# MDL_FUENTE_5V.net
KiCad netlist of a schematic drawn in Altium Designer
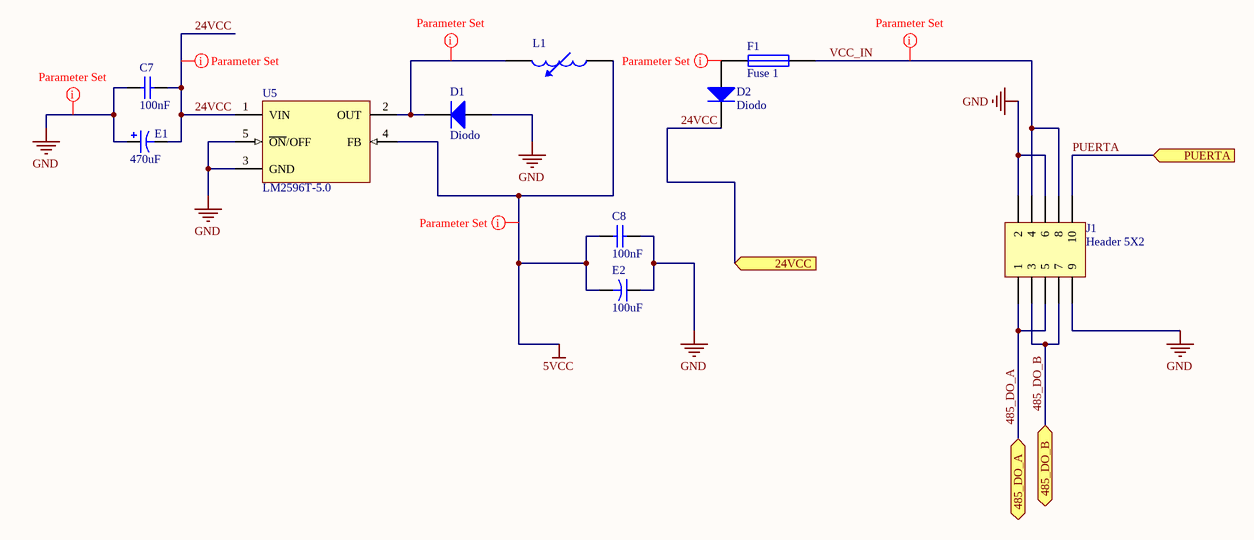
[diagram p0: MDL_FUENTE_5V.SchDoc]

(export (version "E")
  (design (tool "Eeschema 10.0.6"))
  (components
    (comp (ref "C7")
      (value "100nF")
      (footprint "VP44-2.5")
      (description "Dipped Radial Multilayer Ceramic Capacitor X7R: 220nF, 100V")
      (fields (field (name "Comment") "VP44BY224JB") (field (name "PUBLISHER") "Altium Limited"))
      (libsource (lib "Vishay Vitramon Ceramic Dipped Capacitor") (part "VP44BY224JB"))
    )
    (comp (ref "C8")
      (value "100nF")
      (footprint "VP44-2.5")
      (description "Dipped Radial Multilayer Ceramic Capacitor X7R: 220nF, 100V")
      (fields (field (name "Comment") "VP44BY224JB") (field (name "PUBLISHER") "Altium Limited"))
      (libsource (lib "Vishay Vitramon Ceramic Dipped Capacitor") (part "VP44BY224JB"))
    )
    (comp (ref "D1")
      (value "Diodo")
      (footprint "1N4000")
      (description "Diodo rectificador")
      (libsource (lib "Diodos") (part "Diodo"))
    )
    (comp (ref "D2")
      (value "Diodo")
      (footprint "1N4000")
      (description "Diodo rectificador")
      (libsource (lib "Diodos") (part "Diodo"))
    )
    (comp (ref "E1")
      (value "470uF")
      (footprint "C1000UF")
      (description "Polarized Capacitor (Radial)")
      (fields (field (name "Comment") "Cap Pol1") (field (name "PUBLISHER") "Altium Limited"))
      (libsource (lib "Miscellaneous Devices") (part "Cap Pol1"))
    )
    (comp (ref "E2")
      (value "100uF")
      (footprint "C1UF")
      (description "Capacitor")
      (fields (field (name "Comment") "Cap2") (field (name "PUBLISHER") "Altium Limited"))
      (libsource (lib "Miscellaneous Devices") (part "Cap2"))
    )
    (comp (ref "F1")
      (value "Fuse 1")
      (footprint "FUSIBLE_BUSMATIC")
      (description "Fuse")
      (fields (field (name "PUBLISHER") "Altium Limited"))
      (libsource (lib "Miscellaneous Devices") (part "Fuse 1"))
    )
    (comp (ref "J1")
      (value "Header 5X2")
      (footprint "FP_CON10")
      (description "Header, 5-Pin, Dual row")
      (fields (field (name "PUBLISHER") "Altium Limited"))
      (libsource (lib "Miscellaneous Connectors") (part "Header 5X2"))
    )
    (comp (ref "L1")
      (value "Inductor Adj")
      (footprint "Inductor_redondo")
      (description "Adjustable Inductor")
      (fields (field (name "PUBLISHER") "Altium Limited"))
      (libsource (lib "Miscellaneous Devices") (part "Inductor Adj"))
    )
    (comp (ref "U5")
      (value "LM2596T-5.0")
      (footprint "FP_LM2596_D_PCB")
      (description "SIMPLE SWITCHER Power Converter 150 KHz 3A Step-Down Voltage Regulator")
      (fields
        (field (name "MANUFACTURER") "National Semiconductor")
        (field (name "DIGIKEYPARTNUMBER") "LM2596T-5.0-ND")
        (field (name "PUBLISHER") "Altium Limited")
      )
      (libsource (lib "NSC Switcher") (part "LM2596T-5.0"))
    )
  )
  (nets
    (net (code "1") (name "/24VCC") (class "Default")
      (node (ref "C7") (pin "1") (pinfunction "1_1") (pintype "passive"))
      (node (ref "D2") (pin "2") (pinfunction "K_2") (pintype "passive"))
      (node (ref "E1") (pin "2") (pinfunction "2_2") (pintype "passive"))
      (node (ref "U5") (pin "1") (pinfunction "VIN_1") (pintype "power_in"))
    )
    (net (code "2") (name "/485_DO_A") (class "Default")
      (node (ref "J1") (pin "1") (pinfunction "1_1") (pintype "passive"))
      (node (ref "J1") (pin "5") (pinfunction "5_5") (pintype "passive"))
    )
    (net (code "3") (name "/485_DO_B") (class "Default")
      (node (ref "J1") (pin "3") (pinfunction "3_3") (pintype "passive"))
      (node (ref "J1") (pin "7") (pinfunction "7_7") (pintype "passive"))
    )
    (net (code "4") (name "/PUERTA") (class "Default")
      (node (ref "J1") (pin "10") (pinfunction "10_10") (pintype "passive"))
    )
    (net (code "5") (name "/VCC_IN") (class "Default")
      (node (ref "F1") (pin "2") (pinfunction "2_2") (pintype "passive"))
      (node (ref "J1") (pin "4") (pinfunction "4_4") (pintype "passive"))
      (node (ref "J1") (pin "8") (pinfunction "8_8") (pintype "passive"))
    )
    (net (code "6") (name "5VCC") (class "Default")
      (node (ref "C8") (pin "2") (pinfunction "2_2") (pintype "passive"))
      (node (ref "E2") (pin "2") (pinfunction "2_2") (pintype "passive"))
      (node (ref "L1") (pin "1") (pinfunction "1_1") (pintype "passive"))
      (node (ref "U5") (pin "4") (pinfunction "FB_4") (pintype "input"))
    )
    (net (code "7") (name "GND") (class "Default")
      (node (ref "C7") (pin "2") (pinfunction "2_2") (pintype "passive"))
      (node (ref "C8") (pin "1") (pinfunction "1_1") (pintype "passive"))
      (node (ref "D1") (pin "1") (pinfunction "A_1") (pintype "passive"))
      (node (ref "E1") (pin "1") (pinfunction "1_1") (pintype "passive"))
      (node (ref "E2") (pin "1") (pinfunction "1_1") (pintype "passive"))
      (node (ref "J1") (pin "2") (pinfunction "2_2") (pintype "passive"))
      (node (ref "J1") (pin "6") (pinfunction "6_6") (pintype "passive"))
      (node (ref "J1") (pin "9") (pinfunction "9_9") (pintype "passive"))
      (node (ref "U5") (pin "3") (pinfunction "GND_3") (pintype "power_in"))
      (node (ref "U5") (pin "5") (pinfunction "~{ON}/OFF_5") (pintype "input"))
    )
    (net (code "8") (name "Net-(D1-K)") (class "Default")
      (node (ref "D1") (pin "2") (pinfunction "K_2") (pintype "passive"))
      (node (ref "L1") (pin "2") (pinfunction "2_2") (pintype "passive"))
      (node (ref "U5") (pin "2") (pinfunction "OUT_2") (pintype "power_in"))
    )
    (net (code "9") (name "Net-(D2-A)") (class "Default")
      (node (ref "D2") (pin "1") (pinfunction "A_1") (pintype "passive"))
      (node (ref "F1") (pin "1") (pinfunction "1_1") (pintype "passive"))
    )
  )
)
